# imu_minized.net
KiCad netlist of a schematic drawn in EAGLE
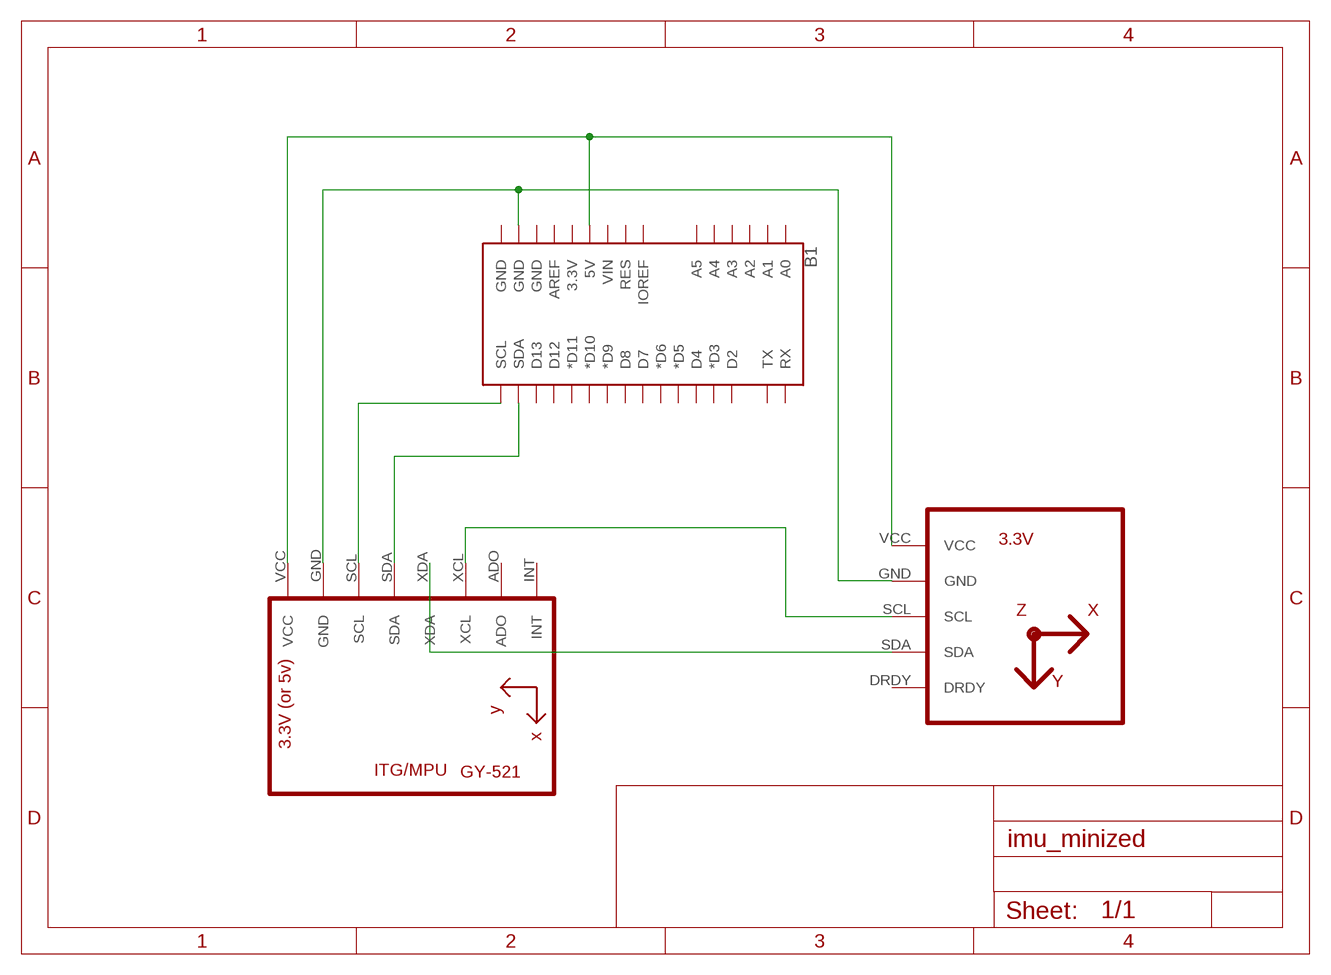
[diagram p0: schematic, sheet 1]

(export (version "E")
  (design (tool "Eeschema 10.0.6"))
  (components
    (comp (ref "B1")
      (value "ARDUINO_UNO_R3_SHIELDNOLABELS")
      (footprint "eagle-import:UNO_R3_SHIELD_NOLABELS")
      (libsource (lib "eagle-import") (part "ARDUINO_UNO_R3_SHIELDNOLABELS"))
    )
    (comp (ref "U1")
      (value "GY-521MPU6050")
      (footprint "eagle-import:GY-521")
      (libsource (lib "eagle-import") (part "GY-521MPU6050"))
    )
    (comp (ref "U2")
      (value "HMC5883LGY-271")
      (footprint "eagle-import:GY-271")
      (libsource (lib "eagle-import") (part "HMC5883LGY-271"))
    )
  )
  (nets
    (net (code "1") (name "Net-(B1-GND-PadGND@1)") (class "Default")
      (node (ref "B1") (pin "GND@1") (pinfunction "GND_GND@1") (pintype "bidirectional"))
      (node (ref "U1") (pin "GND") (pinfunction "GND_GND") (pintype "bidirectional"))
      (node (ref "U2") (pin "GND") (pinfunction "GND_GND") (pintype "bidirectional"))
    )
    (net (code "2") (name "Net-(B1-Pad5V)") (class "Default")
      (node (ref "B1") (pin "5V") (pinfunction "5V_5V") (pintype "bidirectional"))
      (node (ref "U1") (pin "VCC") (pinfunction "VCC_VCC") (pintype "bidirectional"))
      (node (ref "U2") (pin "VCC") (pinfunction "VCC_VCC") (pintype "bidirectional"))
    )
    (net (code "3") (name "Net-(B1-PadSCL)") (class "Default")
      (node (ref "B1") (pin "SCL") (pinfunction "SCL_SCL") (pintype "bidirectional"))
      (node (ref "U1") (pin "SCL") (pinfunction "SCL_SCL") (pintype "bidirectional"))
    )
    (net (code "4") (name "Net-(B1-PadSDA)") (class "Default")
      (node (ref "B1") (pin "SDA") (pinfunction "SDA_SDA") (pintype "bidirectional"))
      (node (ref "U1") (pin "SDA") (pinfunction "SDA_SDA") (pintype "bidirectional"))
    )
    (net (code "5") (name "Net-(U1-PadXCL)") (class "Default")
      (node (ref "U1") (pin "XCL") (pinfunction "XCL_XCL") (pintype "bidirectional"))
      (node (ref "U2") (pin "SCL") (pinfunction "SCL_SCL") (pintype "bidirectional"))
    )
    (net (code "6") (name "Net-(U1-PadXDA)") (class "Default")
      (node (ref "U1") (pin "XDA") (pinfunction "XDA_XDA") (pintype "bidirectional"))
      (node (ref "U2") (pin "SDA") (pinfunction "SDA_SDA") (pintype "bidirectional"))
    )
    (net (code "7") (name "unconnected-(B1-*D3-PadD3)") (class "Default")
      (node (ref "B1") (pin "D3") (pinfunction "*D3_D3") (pintype "bidirectional"))
    )
    (net (code "8") (name "unconnected-(B1-*D5-PadD5)") (class "Default")
      (node (ref "B1") (pin "D5") (pinfunction "*D5_D5") (pintype "bidirectional"))
    )
    (net (code "9") (name "unconnected-(B1-*D6-PadD6)") (class "Default")
      (node (ref "B1") (pin "D6") (pinfunction "*D6_D6") (pintype "bidirectional"))
    )
    (net (code "10") (name "unconnected-(B1-*D9-PadD9)") (class "Default")
      (node (ref "B1") (pin "D9") (pinfunction "*D9_D9") (pintype "bidirectional"))
    )
    (net (code "11") (name "unconnected-(B1-*D10-PadD10)") (class "Default")
      (node (ref "B1") (pin "D10") (pinfunction "*D10_D10") (pintype "bidirectional"))
    )
    (net (code "12") (name "unconnected-(B1-*D11-PadD11)") (class "Default")
      (node (ref "B1") (pin "D11") (pinfunction "*D11_D11") (pintype "bidirectional"))
    )
    (net (code "13") (name "unconnected-(B1-GND-PadGND@0)") (class "Default")
      (node (ref "B1") (pin "GND@0") (pinfunction "GND_GND@0") (pintype "bidirectional"))
    )
    (net (code "14") (name "unconnected-(B1-GND-PadGND@2)") (class "Default")
      (node (ref "B1") (pin "GND@2") (pinfunction "GND_GND@2") (pintype "bidirectional"))
    )
    (net (code "15") (name "unconnected-(B1-Pad3.3V)") (class "Default")
      (node (ref "B1") (pin "3.3V") (pinfunction "3.3V_3.3V") (pintype "bidirectional"))
    )
    (net (code "16") (name "unconnected-(B1-PadA0)") (class "Default")
      (node (ref "B1") (pin "A0") (pinfunction "A0_A0") (pintype "bidirectional"))
    )
    (net (code "17") (name "unconnected-(B1-PadA1)") (class "Default")
      (node (ref "B1") (pin "A1") (pinfunction "A1_A1") (pintype "bidirectional"))
    )
    (net (code "18") (name "unconnected-(B1-PadA2)") (class "Default")
      (node (ref "B1") (pin "A2") (pinfunction "A2_A2") (pintype "bidirectional"))
    )
    (net (code "19") (name "unconnected-(B1-PadA3)") (class "Default")
      (node (ref "B1") (pin "A3") (pinfunction "A3_A3") (pintype "bidirectional"))
    )
    (net (code "20") (name "unconnected-(B1-PadA4)") (class "Default")
      (node (ref "B1") (pin "A4") (pinfunction "A4_A4") (pintype "bidirectional"))
    )
    (net (code "21") (name "unconnected-(B1-PadA5)") (class "Default")
      (node (ref "B1") (pin "A5") (pinfunction "A5_A5") (pintype "bidirectional"))
    )
    (net (code "22") (name "unconnected-(B1-PadAREF)") (class "Default")
      (node (ref "B1") (pin "AREF") (pinfunction "AREF_AREF") (pintype "bidirectional"))
    )
    (net (code "23") (name "unconnected-(B1-PadD2)") (class "Default")
      (node (ref "B1") (pin "D2") (pinfunction "D2_D2") (pintype "bidirectional"))
    )
    (net (code "24") (name "unconnected-(B1-PadD4)") (class "Default")
      (node (ref "B1") (pin "D4") (pinfunction "D4_D4") (pintype "bidirectional"))
    )
    (net (code "25") (name "unconnected-(B1-PadD7)") (class "Default")
      (node (ref "B1") (pin "D7") (pinfunction "D7_D7") (pintype "bidirectional"))
    )
    (net (code "26") (name "unconnected-(B1-PadD8)") (class "Default")
      (node (ref "B1") (pin "D8") (pinfunction "D8_D8") (pintype "bidirectional"))
    )
    (net (code "27") (name "unconnected-(B1-PadD12)") (class "Default")
      (node (ref "B1") (pin "D12") (pinfunction "D12_D12") (pintype "bidirectional"))
    )
    (net (code "28") (name "unconnected-(B1-PadD13)") (class "Default")
      (node (ref "B1") (pin "D13") (pinfunction "D13_D13") (pintype "bidirectional"))
    )
    (net (code "29") (name "unconnected-(B1-PadIOREF)") (class "Default")
      (node (ref "B1") (pin "IOREF") (pinfunction "IOREF_IOREF") (pintype "bidirectional"))
    )
    (net (code "30") (name "unconnected-(B1-PadRES)") (class "Default")
      (node (ref "B1") (pin "RES") (pinfunction "RES_RES") (pintype "bidirectional"))
    )
    (net (code "31") (name "unconnected-(B1-PadRX)") (class "Default")
      (node (ref "B1") (pin "RX") (pinfunction "RX_RX") (pintype "bidirectional"))
    )
    (net (code "32") (name "unconnected-(B1-PadTX)") (class "Default")
      (node (ref "B1") (pin "TX") (pinfunction "TX_TX") (pintype "bidirectional"))
    )
    (net (code "33") (name "unconnected-(B1-PadVIN)") (class "Default")
      (node (ref "B1") (pin "VIN") (pinfunction "VIN_VIN") (pintype "bidirectional"))
    )
    (net (code "34") (name "unconnected-(U1-PadADO)") (class "Default")
      (node (ref "U1") (pin "ADO") (pinfunction "ADO_ADO") (pintype "bidirectional"))
    )
    (net (code "35") (name "unconnected-(U1-PadINT)") (class "Default")
      (node (ref "U1") (pin "INT") (pinfunction "INT_INT") (pintype "bidirectional"))
    )
    (net (code "36") (name "unconnected-(U2-PadDRDY)") (class "Default")
      (node (ref "U2") (pin "DRDY") (pinfunction "DRDY_DRDY") (pintype "bidirectional"))
    )
  )
)
